# 20720.net
KiCad netlist of a schematic drawn in Altium Designer
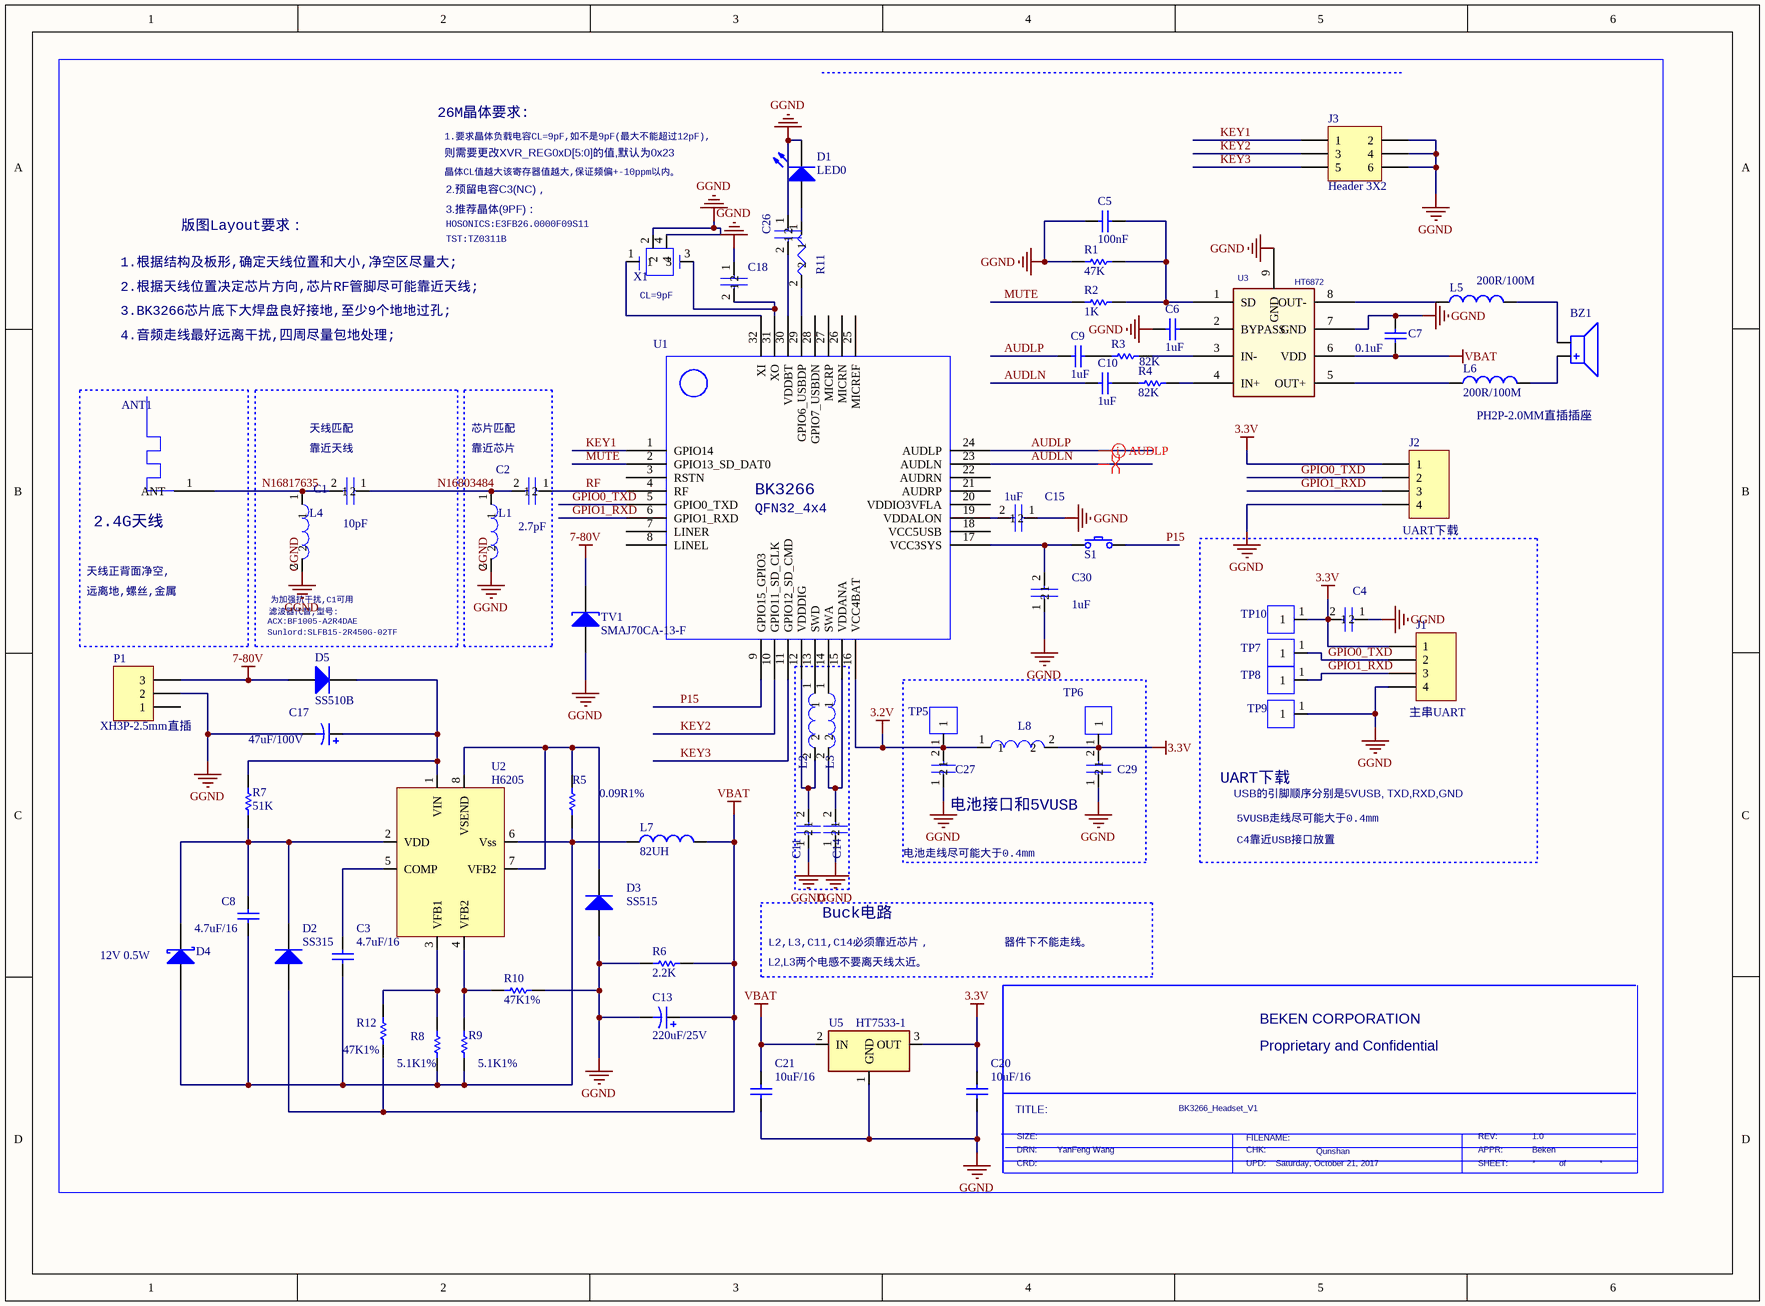
[diagram p0: 平衡车模块20720.SchDoc]

(export (version "E")
  (design (tool "Eeschema 10.0.6"))
  (components
    (comp (ref "ANT1") (value "ANT_2G4") (footprint "BT_NAMI_2") (libsource (lib "*") (part "ANT_2G4")))
    (comp (ref "BZ1")
      (value "PH2P-2.0MM直插插座")
      (footprint "2PIN-2.0")
      (description "Buzzer")
      (libsource (lib "MyLibrary") (part "BUZZER"))
    )
    (comp (ref "C1")
      (value "10pF")
      (footprint "LC-0603_C")
      (fields (field (name "MANUFACTURER") "AVX") (field (name "MANUFACTURER_PART_NUMBER") "0805ZC105KAT2A"))
      (libsource (lib "*") (part "C0603_1"))
    )
    (comp (ref "C2")
      (value "2.7pF")
      (footprint "LC-0603_C")
      (fields (field (name "MANUFACTURER") "AVX") (field (name "MANUFACTURER_PART_NUMBER") "0805ZC105KAT2A"))
      (libsource (lib "*") (part "C0603_1"))
    )
    (comp (ref "C3")
      (value "4.7uF/16")
      (footprint "LC-0805_C")
      (description "Capacitor")
      (fields (field (name "PUBLISHER") "Altium Limited"))
      (libsource (lib "Miscellaneous Devices") (part "Cap"))
    )
    (comp (ref "C4")
      (value "AVX__1.01_UF_0603")
      (fields (field (name "MANUFACTURER") "AVX") (field (name "MANUFACTURER_PART_NUMBER") "06035C103KAt2A"))
      (libsource (lib "*") (part "AVX__1.01_UF_0603"))
    )
    (comp (ref "C5")
      (value "100nF")
      (footprint "LC-0603_C")
      (description "Capacitor")
      (fields (field (name "PUBLISHER") "Altium Limited"))
      (libsource (lib "Miscellaneous Devices") (part "Cap"))
    )
    (comp (ref "C6")
      (value "1uF")
      (footprint "LC-0603_C")
      (description "Capacitor")
      (fields (field (name "PUBLISHER") "Altium Limited"))
      (libsource (lib "Miscellaneous Devices") (part "Cap"))
    )
    (comp (ref "C7")
      (value "0.1uF")
      (footprint "LC-0603_C")
      (description "Capacitor")
      (fields (field (name "PUBLISHER") "Altium Limited"))
      (libsource (lib "Miscellaneous Devices") (part "Cap"))
    )
    (comp (ref "C8")
      (value "4.7uF/16")
      (footprint "LC-0805_C")
      (description "Capacitor")
      (fields (field (name "PUBLISHER") "Altium Limited"))
      (libsource (lib "Miscellaneous Devices") (part "Cap"))
    )
    (comp (ref "C9")
      (value "1uF")
      (footprint "LC-0603_C")
      (description "Capacitor")
      (fields (field (name "PUBLISHER") "Altium Limited"))
      (libsource (lib "Miscellaneous Devices") (part "Cap"))
    )
    (comp (ref "C10")
      (value "1uF")
      (footprint "LC-0603_C")
      (description "Capacitor")
      (fields (field (name "PUBLISHER") "Altium Limited"))
      (libsource (lib "Miscellaneous Devices") (part "Cap"))
    )
    (comp (ref "C11")
      (value "4.7uF/0603")
      (footprint "LC-0603_C")
      (fields (field (name "MANUFACTURER") "AVX") (field (name "MANUFACTURER_PART_NUMBER") "06035C103KAt2A"))
      (libsource (lib "*") (part "AVX__1.01_UF_0603"))
    )
    (comp (ref "C13")
      (value "220uF/25V")
      (footprint "R3.5/8")
      (description "Polarized Capacitor (Radial)")
      (fields (field (name "PUBLISHER") "Altium Limited"))
      (libsource (lib "Miscellaneous Devices") (part "Cap Pol1"))
    )
    (comp (ref "C14")
      (value "4.7uF/0603")
      (footprint "LC-0603_C")
      (fields (field (name "MANUFACTURER") "AVX") (field (name "MANUFACTURER_PART_NUMBER") "06035C103KAt2A"))
      (libsource (lib "*") (part "AVX__1.01_UF_0603"))
    )
    (comp (ref "C15")
      (value "1uF")
      (footprint "LC-0603_C")
      (fields (field (name "MANUFACTURER") "AVX") (field (name "MANUFACTURER_PART_NUMBER") "0805ZC105KAT2A"))
      (libsource (lib "*") (part "C0603_1"))
    )
    (comp (ref "C17")
      (value "47uF/100V")
      (footprint "R3.5/8")
      (description "Polarized Capacitor (Radial)")
      (fields (field (name "PUBLISHER") "Altium Limited"))
      (libsource (lib "Miscellaneous Devices") (part "Cap Pol1"))
    )
    (comp (ref "C18")
      (value "10pF")
      (footprint "LC-0603_C")
      (fields (field (name "MANUFACTURER") "AVX") (field (name "MANUFACTURER_PART_NUMBER") "0805ZC105KAT2A"))
      (libsource (lib "*") (part "C0603_1"))
    )
    (comp (ref "C20")
      (value "10uF/16")
      (footprint "LC-0805_C")
      (description "Capacitor")
      (fields (field (name "PUBLISHER") "Altium Limited"))
      (libsource (lib "Miscellaneous Devices") (part "Cap"))
    )
    (comp (ref "C21")
      (value "10uF/16")
      (footprint "LC-0805_C")
      (description "Capacitor")
      (fields (field (name "PUBLISHER") "Altium Limited"))
      (libsource (lib "Miscellaneous Devices") (part "Cap"))
    )
    (comp (ref "C26")
      (value "1uF")
      (footprint "LC-0603_C")
      (fields (field (name "MANUFACTURER") "AVX") (field (name "MANUFACTURER_PART_NUMBER") "0805ZC105KAT2A"))
      (libsource (lib "*") (part "C0603_1"))
    )
    (comp (ref "C27")
      (value "0.1uF")
      (footprint "LC-0603_C")
      (fields (field (name "MANUFACTURER") "AVX") (field (name "MANUFACTURER_PART_NUMBER") "06035C103KAt2A"))
      (libsource (lib "*") (part "AVX__1.01_UF_0603"))
    )
    (comp (ref "C29")
      (value "0.1uF")
      (footprint "LC-0603_C")
      (fields (field (name "MANUFACTURER") "AVX") (field (name "MANUFACTURER_PART_NUMBER") "06035C103KAt2A"))
      (libsource (lib "*") (part "AVX__1.01_UF_0603"))
    )
    (comp (ref "C30")
      (value "1uF")
      (footprint "LC-0603_C")
      (fields (field (name "MANUFACTURER") "AVX") (field (name "MANUFACTURER_PART_NUMBER") "0805ZC105KAT2A"))
      (libsource (lib "*") (part "C0603_1"))
    )
    (comp (ref "D1")
      (value "LED0")
      (footprint "LC-0603_LED_S3")
      (description "Typical INFRARED GaAs LED")
      (fields (field (name "PUBLISHER") "Altium Limited"))
      (libsource (lib "Miscellaneous Devices") (part "LED0"))
    )
    (comp (ref "D2")
      (value "SS315")
      (footprint "DO-214AA")
      (description "3 Amp General Purpose Rectifier")
      (fields (field (name "PUBLISHER") "Altium Limited"))
      (libsource (lib "Miscellaneous Devices") (part "Diode 1N5402"))
    )
    (comp (ref "D3")
      (value "SS515")
      (footprint "DO-214AA")
      (description "3 Amp General Purpose Rectifier")
      (fields (field (name "PUBLISHER") "Altium Limited"))
      (libsource (lib "Miscellaneous Devices") (part "Diode 1N5402"))
    )
    (comp (ref "D4")
      (value "12V 0.5W")
      (footprint "LL34/SOD-80")
      (description "Schottky Diode")
      (fields (field (name "PUBLISHER") "Altium Limited"))
      (libsource (lib "Miscellaneous Devices") (part "D Schottky"))
    )
    (comp (ref "D5")
      (value "SS510B")
      (footprint "DO-214AA")
      (description "3 Amp General Purpose Rectifier")
      (fields (field (name "PUBLISHER") "Altium Limited"))
      (libsource (lib "Miscellaneous Devices") (part "Diode 1N5402"))
    )
    (comp (ref "J1")
      (value "主串UART")
      (footprint "4PIN-2.0")
      (description "Header, 4-Pin")
      (fields (field (name "PUBLISHER") "Altium Limited"))
      (libsource (lib "保险箱STM32") (part "Header 4"))
    )
    (comp (ref "J2")
      (value "UART下载")
      (footprint "4P-2.0")
      (description "Header, 4-Pin")
      (fields (field (name "PUBLISHER") "Altium Limited"))
      (libsource (lib "保险箱STM32") (part "Header 4"))
    )
    (comp (ref "J3")
      (value "Header 3X2")
      (footprint "3P*2-2.0")
      (description "Header, 3-Pin, Dual row")
      (fields (field (name "PUBLISHER") "Altium Limited"))
      (libsource (lib "Miscellaneous Connectors") (part "Header 3X2"))
    )
    (comp (ref "L1")
      (value "NC")
      (footprint "LC-0603_L")
      (fields
        (field (name "MANUFACTURER") "COILCRAFT")
        (field (name "MANUFACTURER_PART_NUMBER") "0805HS-030TMBC")
      )
      (libsource (lib "*") (part "INDUCTOR_3NH_0603_1"))
    )
    (comp (ref "L2")
      (value "INDUCTOR_3NH_0603_1")
      (footprint "0805L")
      (fields
        (field (name "MANUFACTURER") "COILCRAFT")
        (field (name "MANUFACTURER_PART_NUMBER") "0805HS-030TMBC")
      )
      (libsource (lib "") (part "INDUCTOR_3NH_0603_1_1"))
    )
    (comp (ref "L3")
      (value "INDUCTOR_3NH_0603_1")
      (footprint "0805L")
      (fields
        (field (name "MANUFACTURER") "COILCRAFT")
        (field (name "MANUFACTURER_PART_NUMBER") "0805HS-030TMBC")
      )
      (libsource (lib "*") (part "INDUCTOR_3NH_0603_1"))
    )
    (comp (ref "L4")
      (value "NC")
      (footprint "LC-0603_L")
      (fields
        (field (name "MANUFACTURER") "COILCRAFT")
        (field (name "MANUFACTURER_PART_NUMBER") "0805HS-030TMBC")
      )
      (libsource (lib "*") (part "INDUCTOR_3NH_0603_1"))
    )
    (comp (ref "L5")
      (value "200R/100M")
      (footprint "LC-0603_L")
      (description "Inductor")
      (fields (field (name "PUBLISHER") "Altium Limited"))
      (libsource (lib "Miscellaneous Devices") (part "Inductor"))
    )
    (comp (ref "L6")
      (value "200R/100M")
      (footprint "LC-0603_L")
      (description "Inductor")
      (fields (field (name "PUBLISHER") "Altium Limited"))
      (libsource (lib "Miscellaneous Devices") (part "Inductor"))
    )
    (comp (ref "L7")
      (value "82UH")
      (footprint "CD104")
      (description "Inductor")
      (fields (field (name "PUBLISHER") "Altium Limited"))
      (libsource (lib "Miscellaneous Devices") (part "Inductor"))
    )
    (comp (ref "L8")
      (value "INDUCTOR_3NH_0603_1")
      (footprint "0805L")
      (fields
        (field (name "MANUFACTURER") "COILCRAFT")
        (field (name "MANUFACTURER_PART_NUMBER") "0805HS-030TMBC")
      )
      (libsource (lib "*") (part "INDUCTOR_3NH_0603_1"))
    )
    (comp (ref "P1")
      (value "XH3P-2.5mm直插")
      (footprint "3P-2.5")
      (description "Header, 3-Pin")
      (fields (field (name "PUBLISHER") "Altium Limited"))
      (libsource (lib "Miscellaneous Connectors") (part "Header 3"))
    )
    (comp (ref "R1")
      (value "47K")
      (footprint "LC-0603_R")
      (description "Resistor")
      (fields (field (name "PUBLISHER") "Altium Limited"))
      (libsource (lib "Miscellaneous Devices") (part "Res1"))
    )
    (comp (ref "R2")
      (value "1K")
      (footprint "LC-0603_R")
      (description "Resistor")
      (fields (field (name "PUBLISHER") "Altium Limited"))
      (libsource (lib "Miscellaneous Devices") (part "Res1"))
    )
    (comp (ref "R3")
      (value "82K")
      (footprint "LC-0603_R")
      (description "Resistor")
      (fields (field (name "PUBLISHER") "Altium Limited"))
      (libsource (lib "Miscellaneous Devices") (part "Res1"))
    )
    (comp (ref "R4")
      (value "82K")
      (footprint "LC-0603_R")
      (description "Resistor")
      (fields (field (name "PUBLISHER") "Altium Limited"))
      (libsource (lib "Miscellaneous Devices") (part "Res1"))
    )
    (comp (ref "R5")
      (value "0.09R1%")
      (footprint "LC-1206_R")
      (description "Resistor")
      (fields (field (name "PUBLISHER") "Altium Limited"))
      (libsource (lib "Miscellaneous Devices") (part "Res1"))
    )
    (comp (ref "R6")
      (value "2.2K")
      (footprint "LC-0603_R")
      (description "Resistor")
      (fields (field (name "PUBLISHER") "Altium Limited"))
      (libsource (lib "Miscellaneous Devices") (part "Res1"))
    )
    (comp (ref "R7")
      (value "51K")
      (footprint "LC-0603_R")
      (description "Resistor")
      (fields (field (name "PUBLISHER") "Altium Limited"))
      (libsource (lib "Miscellaneous Devices") (part "Res1"))
    )
    (comp (ref "R8")
      (value "5.1K1%")
      (footprint "LC-0603_R")
      (description "Resistor")
      (fields (field (name "PUBLISHER") "Altium Limited"))
      (libsource (lib "Miscellaneous Devices") (part "Res1"))
    )
    (comp (ref "R9")
      (value "5.1K1%")
      (footprint "LC-0603_R")
      (description "Resistor")
      (fields (field (name "PUBLISHER") "Altium Limited"))
      (libsource (lib "Miscellaneous Devices") (part "Res1"))
    )
    (comp (ref "R10")
      (value "47K1%")
      (footprint "LC-0603_R")
      (description "Resistor")
      (fields (field (name "PUBLISHER") "Altium Limited"))
      (libsource (lib "Miscellaneous Devices") (part "Res1"))
    )
    (comp (ref "R11")
      (value "200R")
      (footprint "LC-0603_R")
      (fields (field (name "MANUFACTURER") "KOA") (field (name "MANUFACTURER_PART_NUMBER") "RK73H2AT4752F"))
      (libsource (lib "*") (part "KOA_47_1.5K__1%__0805"))
    )
    (comp (ref "R12")
      (value "47K1%")
      (footprint "LC-0603_R")
      (description "Resistor")
      (fields (field (name "PUBLISHER") "Altium Limited"))
      (libsource (lib "Miscellaneous Devices") (part "Res1"))
    )
    (comp (ref "S1")
      (value "SW")
      (footprint "KEY_5.2*3.7*6.4")
      (description "Switch")
      (libsource (lib "保险箱STM32") (part "SW"))
    )
    (comp (ref "TP5")
      (value "1_PIN_TP_HEADER")
      (footprint "1P-1.0mm")
      (fields (field (name "MANUFACTURER") "Crane") (field (name "MANUFACTURER_PART_NUMBER") "PGM01SS-G59"))
      (libsource (lib "*") (part "1_PIN_TP_HEADER"))
    )
    (comp (ref "TP6")
      (value "1_PIN_TP_HEADER")
      (footprint "1P-1.0mm")
      (fields (field (name "MANUFACTURER") "Crane") (field (name "MANUFACTURER_PART_NUMBER") "PGM01SS-G59"))
      (libsource (lib "*") (part "1_PIN_TP_HEADER"))
    )
    (comp (ref "TP7")
      (value "1_PIN_TP_HEADER")
      (footprint "1P-1.0mm")
      (fields (field (name "MANUFACTURER") "Crane") (field (name "MANUFACTURER_PART_NUMBER") "PGM01SS-G59"))
      (libsource (lib "*") (part "1_PIN_TP_HEADER"))
    )
    (comp (ref "TP8")
      (value "1_PIN_TP_HEADER")
      (footprint "1P-1.0mm")
      (fields (field (name "MANUFACTURER") "Crane") (field (name "MANUFACTURER_PART_NUMBER") "PGM01SS-G59"))
      (libsource (lib "*") (part "1_PIN_TP_HEADER"))
    )
    (comp (ref "TP9")
      (value "1_PIN_TP_HEADER")
      (footprint "1P-1.0mm")
      (fields (field (name "MANUFACTURER") "Crane") (field (name "MANUFACTURER_PART_NUMBER") "PGM01SS-G59"))
      (libsource (lib "*") (part "1_PIN_TP_HEADER"))
    )
    (comp (ref "TP10")
      (value "1_PIN_TP_HEADER")
      (footprint "1P-1.0mm")
      (fields (field (name "MANUFACTURER") "Crane") (field (name "MANUFACTURER_PART_NUMBER") "PGM01SS-G59"))
      (libsource (lib "*") (part "1_PIN_TP_HEADER"))
    )
    (comp (ref "TV1")
      (value "SMAJ70CA-13-F")
      (footprint "DO-214AA")
      (description "Tunnel Diode - RLC Model")
      (fields (field (name "PUBLISHER") "Altium Limited"))
      (libsource (lib "Miscellaneous Devices") (part "D Tunnel1"))
    )
    (comp (ref "U1")
      (value "BK3266_QFN32_5")
      (footprint "LC-VQFN-32_4x4x04P")
      (libsource (lib "*") (part "BK3266_QFN32_5"))
    )
    (comp (ref "U2") (value "H6205") (footprint "ESOP8") (libsource (lib "平衡车+蓝牙模块") (part "H6205")))
    (comp (ref "U3") (value "HT6872") (footprint "SOP8-LW") (libsource (lib "*") (part "AM24LC02_0")))
    (comp (ref "U5") (value "HT7533-1") (footprint "SOT-89-3") (libsource (lib "*") (part "XC6206P302M")))
    (comp (ref "X1") (value "XTAL_16MHZ") (footprint "XTAL3225") (libsource (lib "*") (part "XTAL_16MHZ")))
  )
  (nets
    (net (code "1") (name "/AUDLN") (class "Default")
      (node (ref "C10") (pin "1") (pinfunction "1_1") (pintype "passive"))
      (node (ref "U1") (pin "23") (pinfunction "AUDLN_23") (pintype "passive"))
    )
    (net (code "2") (name "/AUDLP") (class "Default")
      (node (ref "C9") (pin "1") (pinfunction "1_1") (pintype "passive"))
      (node (ref "U1") (pin "24") (pinfunction "AUDLP_24") (pintype "passive"))
    )
    (net (code "3") (name "/GPIO0_TXD") (class "Default")
      (node (ref "J1") (pin "2") (pinfunction "2_2") (pintype "passive"))
      (node (ref "J2") (pin "2") (pinfunction "2_2") (pintype "passive"))
      (node (ref "TP7") (pin "1") (pinfunction "1_1") (pintype "passive"))
      (node (ref "U1") (pin "5") (pinfunction "GPIO0_TXD_5") (pintype "passive"))
    )
    (net (code "4") (name "/GPIO1_RXD") (class "Default")
      (node (ref "J1") (pin "3") (pinfunction "3_3") (pintype "passive"))
      (node (ref "J2") (pin "3") (pinfunction "3_3") (pintype "passive"))
      (node (ref "TP8") (pin "1") (pinfunction "1_1") (pintype "passive"))
      (node (ref "U1") (pin "6") (pinfunction "GPIO1_RXD_6") (pintype "passive"))
    )
    (net (code "5") (name "/KEY1") (class "Default")
      (node (ref "J3") (pin "1") (pinfunction "1_1") (pintype "passive"))
      (node (ref "U1") (pin "1") (pinfunction "GPIO14_1") (pintype "passive"))
    )
    (net (code "6") (name "/KEY2") (class "Default")
      (node (ref "J3") (pin "3") (pinfunction "3_3") (pintype "passive"))
      (node (ref "U1") (pin "10") (pinfunction "GPIO11_SD_CLK_10") (pintype "passive"))
    )
    (net (code "7") (name "/KEY3") (class "Default")
      (node (ref "J3") (pin "5") (pinfunction "5_5") (pintype "passive"))
      (node (ref "U1") (pin "11") (pinfunction "GPIO12_SD_CMD_11") (pintype "passive"))
    )
    (net (code "8") (name "/MUTE") (class "Default")
      (node (ref "R2") (pin "1") (pinfunction "1_1") (pintype "passive"))
      (node (ref "U1") (pin "2") (pinfunction "GPIO13_SD_DAT0_2") (pintype "passive"))
    )
    (net (code "9") (name "/N16803484") (class "Default")
      (node (ref "C1") (pin "1") (pinfunction "1_1") (pintype "passive"))
      (node (ref "C2") (pin "2") (pinfunction "2_2") (pintype "passive"))
      (node (ref "L1") (pin "1") (pinfunction "1_1") (pintype "passive"))
    )
    (net (code "10") (name "/N16817635") (class "Default")
      (node (ref "ANT1") (pin "1") (pinfunction "ANT_1") (pintype "passive"))
      (node (ref "C1") (pin "2") (pinfunction "2_2") (pintype "passive"))
      (node (ref "L4") (pin "1") (pinfunction "1_1") (pintype "passive"))
    )
    (net (code "11") (name "/P15") (class "Default")
      (node (ref "S1") (pin "2") (pintype "passive"))
      (node (ref "U1") (pin "9") (pinfunction "GPIO15_GPIO3_9") (pintype "passive"))
    )
    (net (code "12") (name "/RF") (class "Default")
      (node (ref "C2") (pin "1") (pinfunction "1_1") (pintype "passive"))
      (node (ref "U1") (pin "4") (pinfunction "RF_4") (pintype "passive"))
    )
    (net (code "13") (name "3.2V") (class "Default")
      (node (ref "C27") (pin "2") (pinfunction "2_2") (pintype "passive"))
      (node (ref "L8") (pin "1") (pinfunction "1_1") (pintype "passive"))
      (node (ref "TP5") (pin "1") (pinfunction "1_1") (pintype "passive"))
      (node (ref "U1") (pin "16") (pinfunction "VCC4BAT_16") (pintype "passive"))
    )
    (net (code "14") (name "3.3V") (class "Default")
      (node (ref "C20") (pin "2") (pinfunction "2_2") (pintype "passive"))
      (node (ref "C29") (pin "2") (pinfunction "2_2") (pintype "passive"))
      (node (ref "C4") (pin "2") (pinfunction "2_2") (pintype "passive"))
      (node (ref "J1") (pin "1") (pinfunction "1_1") (pintype "passive"))
      (node (ref "J2") (pin "1") (pinfunction "1_1") (pintype "passive"))
      (node (ref "L8") (pin "2") (pinfunction "2_2") (pintype "passive"))
      (node (ref "TP10") (pin "1") (pinfunction "1_1") (pintype "passive"))
      (node (ref "TP6") (pin "1") (pinfunction "1_1") (pintype "passive"))
      (node (ref "U5") (pin "3") (pinfunction "OUT_3") (pintype "passive"))
    )
    (net (code "15") (name "7-80V") (class "Default")
      (node (ref "D5") (pin "1") (pinfunction "A_1") (pintype "passive"))
      (node (ref "P1") (pin "3") (pinfunction "3_3") (pintype "passive"))
      (node (ref "TV1") (pin "2") (pinfunction "K_2") (pintype "passive"))
    )
    (net (code "16") (name "GGND") (class "Default")
      (node (ref "C11") (pin "1") (pinfunction "1_1") (pintype "passive"))
      (node (ref "C13") (pin "2") (pinfunction "2_2") (pintype "passive"))
      (node (ref "C14") (pin "1") (pinfunction "1_1") (pintype "passive"))
      (node (ref "C15") (pin "1") (pinfunction "1_1") (pintype "passive"))
      (node (ref "C17") (pin "2") (pinfunction "2_2") (pintype "passive"))
      (node (ref "C18") (pin "1") (pinfunction "1_1") (pintype "passive"))
      (node (ref "C20") (pin "1") (pinfunction "1_1") (pintype "passive"))
      (node (ref "C21") (pin "1") (pinfunction "1_1") (pintype "passive"))
      (node (ref "C26") (pin "1") (pinfunction "1_1") (pintype "passive"))
      (node (ref "C27") (pin "1") (pinfunction "1_1") (pintype "passive"))
      (node (ref "C29") (pin "1") (pinfunction "1_1") (pintype "passive"))
      (node (ref "C30") (pin "1") (pinfunction "1_1") (pintype "passive"))
      (node (ref "C4") (pin "1") (pinfunction "1_1") (pintype "passive"))
      (node (ref "C5") (pin "1") (pinfunction "1_1") (pintype "passive"))
      (node (ref "C6") (pin "1") (pinfunction "1_1") (pintype "passive"))
      (node (ref "C7") (pin "2") (pinfunction "2_2") (pintype "passive"))
      (node (ref "D1") (pin "2") (pinfunction "K_2") (pintype "passive"))
      (node (ref "D3") (pin "1") (pinfunction "A_1") (pintype "passive"))
      (node (ref "J1") (pin "4") (pinfunction "4_4") (pintype "passive"))
      (node (ref "J2") (pin "4") (pinfunction "4_4") (pintype "passive"))
      (node (ref "J3") (pin "2") (pinfunction "2_2") (pintype "passive"))
      (node (ref "J3") (pin "4") (pinfunction "4_4") (pintype "passive"))
      (node (ref "J3") (pin "6") (pinfunction "6_6") (pintype "passive"))
      (node (ref "L1") (pin "2") (pinfunction "2_2") (pintype "passive"))
      (node (ref "L4") (pin "2") (pinfunction "2_2") (pintype "passive"))
      (node (ref "P1") (pin "2") (pinfunction "2_2") (pintype "passive"))
      (node (ref "R1") (pin "1") (pinfunction "1_1") (pintype "passive"))
      (node (ref "R10") (pin "2") (pinfunction "2_2") (pintype "passive"))
      (node (ref "R6") (pin "2") (pinfunction "2_2") (pintype "passive"))
      (node (ref "TP9") (pin "1") (pinfunction "1_1") (pintype "passive"))
      (node (ref "TV1") (pin "1") (pinfunction "A_1") (pintype "passive"))
      (node (ref "U1") (pin "33") (pinfunction "GGND_33") (pintype "power_in"))
      (node (ref "U3") (pin "7") (pinfunction "GND_7") (pintype "passive"))
      (node (ref "U3") (pin "9") (pinfunction "GND_9") (pintype "passive"))
      (node (ref "U5") (pin "1") (pinfunction "GND_1") (pintype "passive"))
      (node (ref "X1") (pin "2") (pinfunction "2_2") (pintype "passive"))
      (node (ref "X1") (pin "4") (pinfunction "4_4") (pintype "passive"))
    )
    (net (code "17") (name "Net-(BZ1-Pad1)") (class "Default")
      (node (ref "BZ1") (pin "1") (pintype "passive"))
      (node (ref "L6") (pin "2") (pinfunction "2_2") (pintype "passive"))
    )
    (net (code "18") (name "Net-(BZ1-Pad2)") (class "Default")
      (node (ref "BZ1") (pin "2") (pintype "passive"))
      (node (ref "L5") (pin "2") (pinfunction "2_2") (pintype "passive"))
    )
    (net (code "19") (name "Net-(C9-Pad2)") (class "Default")
      (node (ref "C9") (pin "2") (pinfunction "2_2") (pintype "passive"))
      (node (ref "R3") (pin "1") (pinfunction "1_1") (pintype "passive"))
    )
    (net (code "20") (name "Net-(C10-Pad2)") (class "Default")
      (node (ref "C10") (pin "2") (pinfunction "2_2") (pintype "passive"))
      (node (ref "R4") (pin "1") (pinfunction "1_1") (pintype "passive"))
    )
    (net (code "21") (name "Net-(D1-A)") (class "Default")
      (node (ref "D1") (pin "1") (pinfunction "A_1") (pintype "passive"))
      (node (ref "R11") (pin "1") (pinfunction "1_1") (pintype "passive"))
    )
    (net (code "22") (name "Net-(D2-K)") (class "Default")
      (node (ref "C8") (pin "2") (pinfunction "2_2") (pintype "passive"))
      (node (ref "D2") (pin "2") (pinfunction "K_2") (pintype "passive"))
      (node (ref "D4") (pin "2") (pinfunction "K_2") (pintype "passive"))
      (node (ref "R7") (pin "1") (pinfunction "1_1") (pintype "passive"))
      (node (ref "U2") (pin "2") (pinfunction "VDD_2") (pintype "passive"))
    )
    (net (code "23") (name "Net-(D3-K)") (class "Default")
      (node (ref "D3") (pin "2") (pinfunction "K_2") (pintype "passive"))
      (node (ref "R5") (pin "2") (pinfunction "2_2") (pintype "passive"))
      (node (ref "U2") (pin "7") (pinfunction "VFB2_7") (pintype "passive"))
      (node (ref "U2") (pin "8") (pinfunction "VSEND_8") (pintype "passive"))
    )
    (net (code "24") (name "Net-(D4-A)") (class "Default")
      (node (ref "C3") (pin "1") (pinfunction "1_1") (pintype "passive"))
      (node (ref "C8") (pin "1") (pinfunction "1_1") (pintype "passive"))
      (node (ref "D4") (pin "1") (pinfunction "A_1") (pintype "passive"))
      (node (ref "L7") (pin "1") (pinfunction "1_1") (pintype "passive"))
      (node (ref "R5") (pin "1") (pinfunction "1_1") (pintype "passive"))
      (node (ref "R8") (pin "2") (pinfunction "2_2") (pintype "passive"))
      (node (ref "R9") (pin "2") (pinfunction "2_2") (pintype "passive"))
      (node (ref "U2") (pin "6") (pinfunction "Vss_6") (pintype "passive"))
    )
    (net (code "25") (name "Net-(D5-K)") (class "Default")
      (node (ref "C17") (pin "1") (pinfunction "1_1") (pintype "passive"))
      (node (ref "D5") (pin "2") (pinfunction "K_2") (pintype "passive"))
      (node (ref "R7") (pin "2") (pinfunction "2_2") (pintype "passive"))
      (node (ref "U2") (pin "1") (pinfunction "VIN_1") (pintype "passive"))
    )
    (net (code "26") (name "Net-(R10-Pad1)") (class "Default")
      (node (ref "R10") (pin "1") (pinfunction "1_1") (pintype "passive"))
      (node (ref "R9") (pin "1") (pinfunction "1_1") (pintype "passive"))
      (node (ref "U2") (pin "4") (pinfunction "VFB2_4") (pintype "passive"))
    )
    (net (code "27") (name "Net-(U1-GPIO6_USBDP)") (class "Default")
      (node (ref "R11") (pin "2") (pinfunction "2_2") (pintype "passive"))
      (node (ref "U1") (pin "29") (pinfunction "GPIO6_USBDP_29") (pintype "passive"))
    )
    (net (code "28") (name "Net-(U1-SWA)") (class "Default")
      (node (ref "L3") (pin "1") (pinfunction "1_1") (pintype "passive"))
      (node (ref "U1") (pin "14") (pinfunction "SWA_14") (pintype "passive"))
    )
    (net (code "29") (name "Net-(U1-SWD)") (class "Default")
      (node (ref "L2") (pin "1") (pinfunction "1_1") (pintype "passive"))
      (node (ref "U1") (pin "13") (pinfunction "SWD_13") (pintype "passive"))
    )
    (net (code "30") (name "Net-(U1-VCC3SYS)") (class "Default")
      (node (ref "C30") (pin "2") (pinfunction "2_2") (pintype "passive"))
      (node (ref "S1") (pin "1") (pintype "passive"))
      (node (ref "U1") (pin "17") (pinfunction "VCC3SYS_17") (pintype "passive"))
    )
    (net (code "31") (name "Net-(U1-VDDALON)") (class "Default")
      (node (ref "C15") (pin "2") (pinfunction "2_2") (pintype "passive"))
      (node (ref "U1") (pin "19") (pinfunction "VDDALON_19") (pintype "passive"))
    )
    (net (code "32") (name "Net-(U1-VDDANA)") (class "Default")
      (node (ref "C14") (pin "2") (pinfunction "2_2") (pintype "passive"))
      (node (ref "L3") (pin "2") (pinfunction "2_2") (pintype "passive"))
      (node (ref "U1") (pin "15") (pinfunction "VDDANA_15") (pintype "passive"))
    )
    (net (code "33") (name "Net-(U1-VDDBT)") (class "Default")
      (node (ref "C26") (pin "2") (pinfunction "2_2") (pintype "passive"))
      (node (ref "U1") (pin "30") (pinfunction "VDDBT_30") (pintype "passive"))
    )
    (net (code "34") (name "Net-(U1-VDDDIG)") (class "Default")
      (node (ref "C11") (pin "2") (pinfunction "2_2") (pintype "passive"))
      (node (ref "L2") (pin "2") (pinfunction "2_2") (pintype "passive"))
      (node (ref "U1") (pin "12") (pinfunction "VDDDIG_12") (pintype "passive"))
    )
    (net (code "35") (name "Net-(U1-XI)") (class "Default")
      (node (ref "U1") (pin "32") (pinfunction "XI_32") (pintype "passive"))
      (node (ref "X1") (pin "1") (pinfunction "1_1") (pintype "passive"))
    )
    (net (code "36") (name "Net-(U1-XO)") (class "Default")
      (node (ref "C18") (pin "2") (pinfunction "2_2") (pintype "passive"))
      (node (ref "U1") (pin "31") (pinfunction "XO_31") (pintype "passive"))
      (node (ref "X1") (pin "3") (pinfunction "3_3") (pintype "passive"))
    )
    (net (code "37") (name "Net-(U2-COMP)") (class "Default")
      (node (ref "C3") (pin "2") (pinfunction "2_2") (pintype "passive"))
      (node (ref "U2") (pin "5") (pinfunction "COMP_5") (pintype "passive"))
    )
    (net (code "38") (name "Net-(U2-VFB1)") (class "Default")
      (node (ref "R12") (pin "2") (pinfunction "2_2") (pintype "passive"))
      (node (ref "R8") (pin "1") (pinfunction "1_1") (pintype "passive"))
      (node (ref "U2") (pin "3") (pinfunction "VFB1_3") (pintype "passive"))
    )
    (net (code "39") (name "Net-(U3-BYPASS)") (class "Default")
      (node (ref "C6") (pin "2") (pinfunction "2_2") (pintype "passive"))
      (node (ref "U3") (pin "2") (pinfunction "BYPASS_2") (pintype "passive"))
    )
    (net (code "40") (name "Net-(U3-IN+)") (class "Default")
      (node (ref "R4") (pin "2") (pinfunction "2_2") (pintype "passive"))
      (node (ref "U3") (pin "4") (pinfunction "IN+_4") (pintype "passive"))
    )
    (net (code "41") (name "Net-(U3-IN-)") (class "Default")
      (node (ref "R3") (pin "2") (pinfunction "2_2") (pintype "passive"))
      (node (ref "U3") (pin "3") (pinfunction "IN-_3") (pintype "passive"))
    )
    (net (code "42") (name "Net-(U3-OUT+)") (class "Default")
      (node (ref "L6") (pin "1") (pinfunction "1_1") (pintype "passive"))
      (node (ref "U3") (pin "5") (pinfunction "OUT+_5") (pintype "passive"))
    )
    (net (code "43") (name "Net-(U3-OUT-)") (class "Default")
      (node (ref "L5") (pin "1") (pinfunction "1_1") (pintype "passive"))
      (node (ref "U3") (pin "8") (pinfunction "OUT-_8") (pintype "passive"))
    )
    (net (code "44") (name "Net-(U3-SD)") (class "Default")
      (node (ref "C5") (pin "2") (pinfunction "2_2") (pintype "passive"))
      (node (ref "R1") (pin "2") (pinfunction "2_2") (pintype "passive"))
      (node (ref "R2") (pin "2") (pinfunction "2_2") (pintype "passive"))
      (node (ref "U3") (pin "1") (pinfunction "SD_1") (pintype "passive"))
    )
    (net (code "45") (name "VBAT") (class "Default")
      (node (ref "C13") (pin "1") (pinfunction "1_1") (pintype "passive"))
      (node (ref "C21") (pin "2") (pinfunction "2_2") (pintype "passive"))
      (node (ref "C7") (pin "1") (pinfunction "1_1") (pintype "passive"))
      (node (ref "D2") (pin "1") (pinfunction "A_1") (pintype "passive"))
      (node (ref "L7") (pin "2") (pinfunction "2_2") (pintype "passive"))
      (node (ref "R12") (pin "1") (pinfunction "1_1") (pintype "passive"))
      (node (ref "R6") (pin "1") (pinfunction "1_1") (pintype "passive"))
      (node (ref "U3") (pin "6") (pinfunction "VDD_6") (pintype "passive"))
      (node (ref "U5") (pin "2") (pinfunction "IN_2") (pintype "passive"))
    )
    (net (code "46") (name "unconnected-(P1-Pad1)") (class "Default")
      (node (ref "P1") (pin "1") (pinfunction "1_1") (pintype "passive"))
    )
    (net (code "47") (name "unconnected-(U1-AUDRN-Pad22)") (class "Default")
      (node (ref "U1") (pin "22") (pinfunction "AUDRN_22") (pintype "passive"))
    )
    (net (code "48") (name "unconnected-(U1-AUDRP-Pad21)") (class "Default")
      (node (ref "U1") (pin "21") (pinfunction "AUDRP_21") (pintype "passive"))
    )
    (net (code "49") (name "unconnected-(U1-GPIO7_USBDN-Pad28)") (class "Default")
      (node (ref "U1") (pin "28") (pinfunction "GPIO7_USBDN_28") (pintype "passive"))
    )
    (net (code "50") (name "unconnected-(U1-LINEL-Pad8)") (class "Default")
      (node (ref "U1") (pin "8") (pinfunction "LINEL_8") (pintype "passive"))
    )
    (net (code "51") (name "unconnected-(U1-LINER-Pad7)") (class "Default")
      (node (ref "U1") (pin "7") (pinfunction "LINER_7") (pintype "passive"))
    )
    (net (code "52") (name "unconnected-(U1-MICREF-Pad25)") (class "Default")
      (node (ref "U1") (pin "25") (pinfunction "MICREF_25") (pintype "passive"))
    )
    (net (code "53") (name "unconnected-(U1-MICRN-Pad26)") (class "Default")
      (node (ref "U1") (pin "26") (pinfunction "MICRN_26") (pintype "passive"))
    )
    (net (code "54") (name "unconnected-(U1-MICRP-Pad27)") (class "Default")
      (node (ref "U1") (pin "27") (pinfunction "MICRP_27") (pintype "passive"))
    )
    (net (code "55") (name "unconnected-(U1-RSTN-Pad3)") (class "Default")
      (node (ref "U1") (pin "3") (pinfunction "RSTN_3") (pintype "passive"))
    )
    (net (code "56") (name "unconnected-(U1-VCC5USB-Pad18)") (class "Default")
      (node (ref "U1") (pin "18") (pinfunction "VCC5USB_18") (pintype "passive"))
    )
    (net (code "57") (name "unconnected-(U1-VDDIO3VFLA-Pad20)") (class "Default")
      (node (ref "U1") (pin "20") (pinfunction "VDDIO3VFLA_20") (pintype "passive"))
    )
  )
)
